# evalboard_v1_final.net
KiCad netlist of a schematic drawn in EAGLE
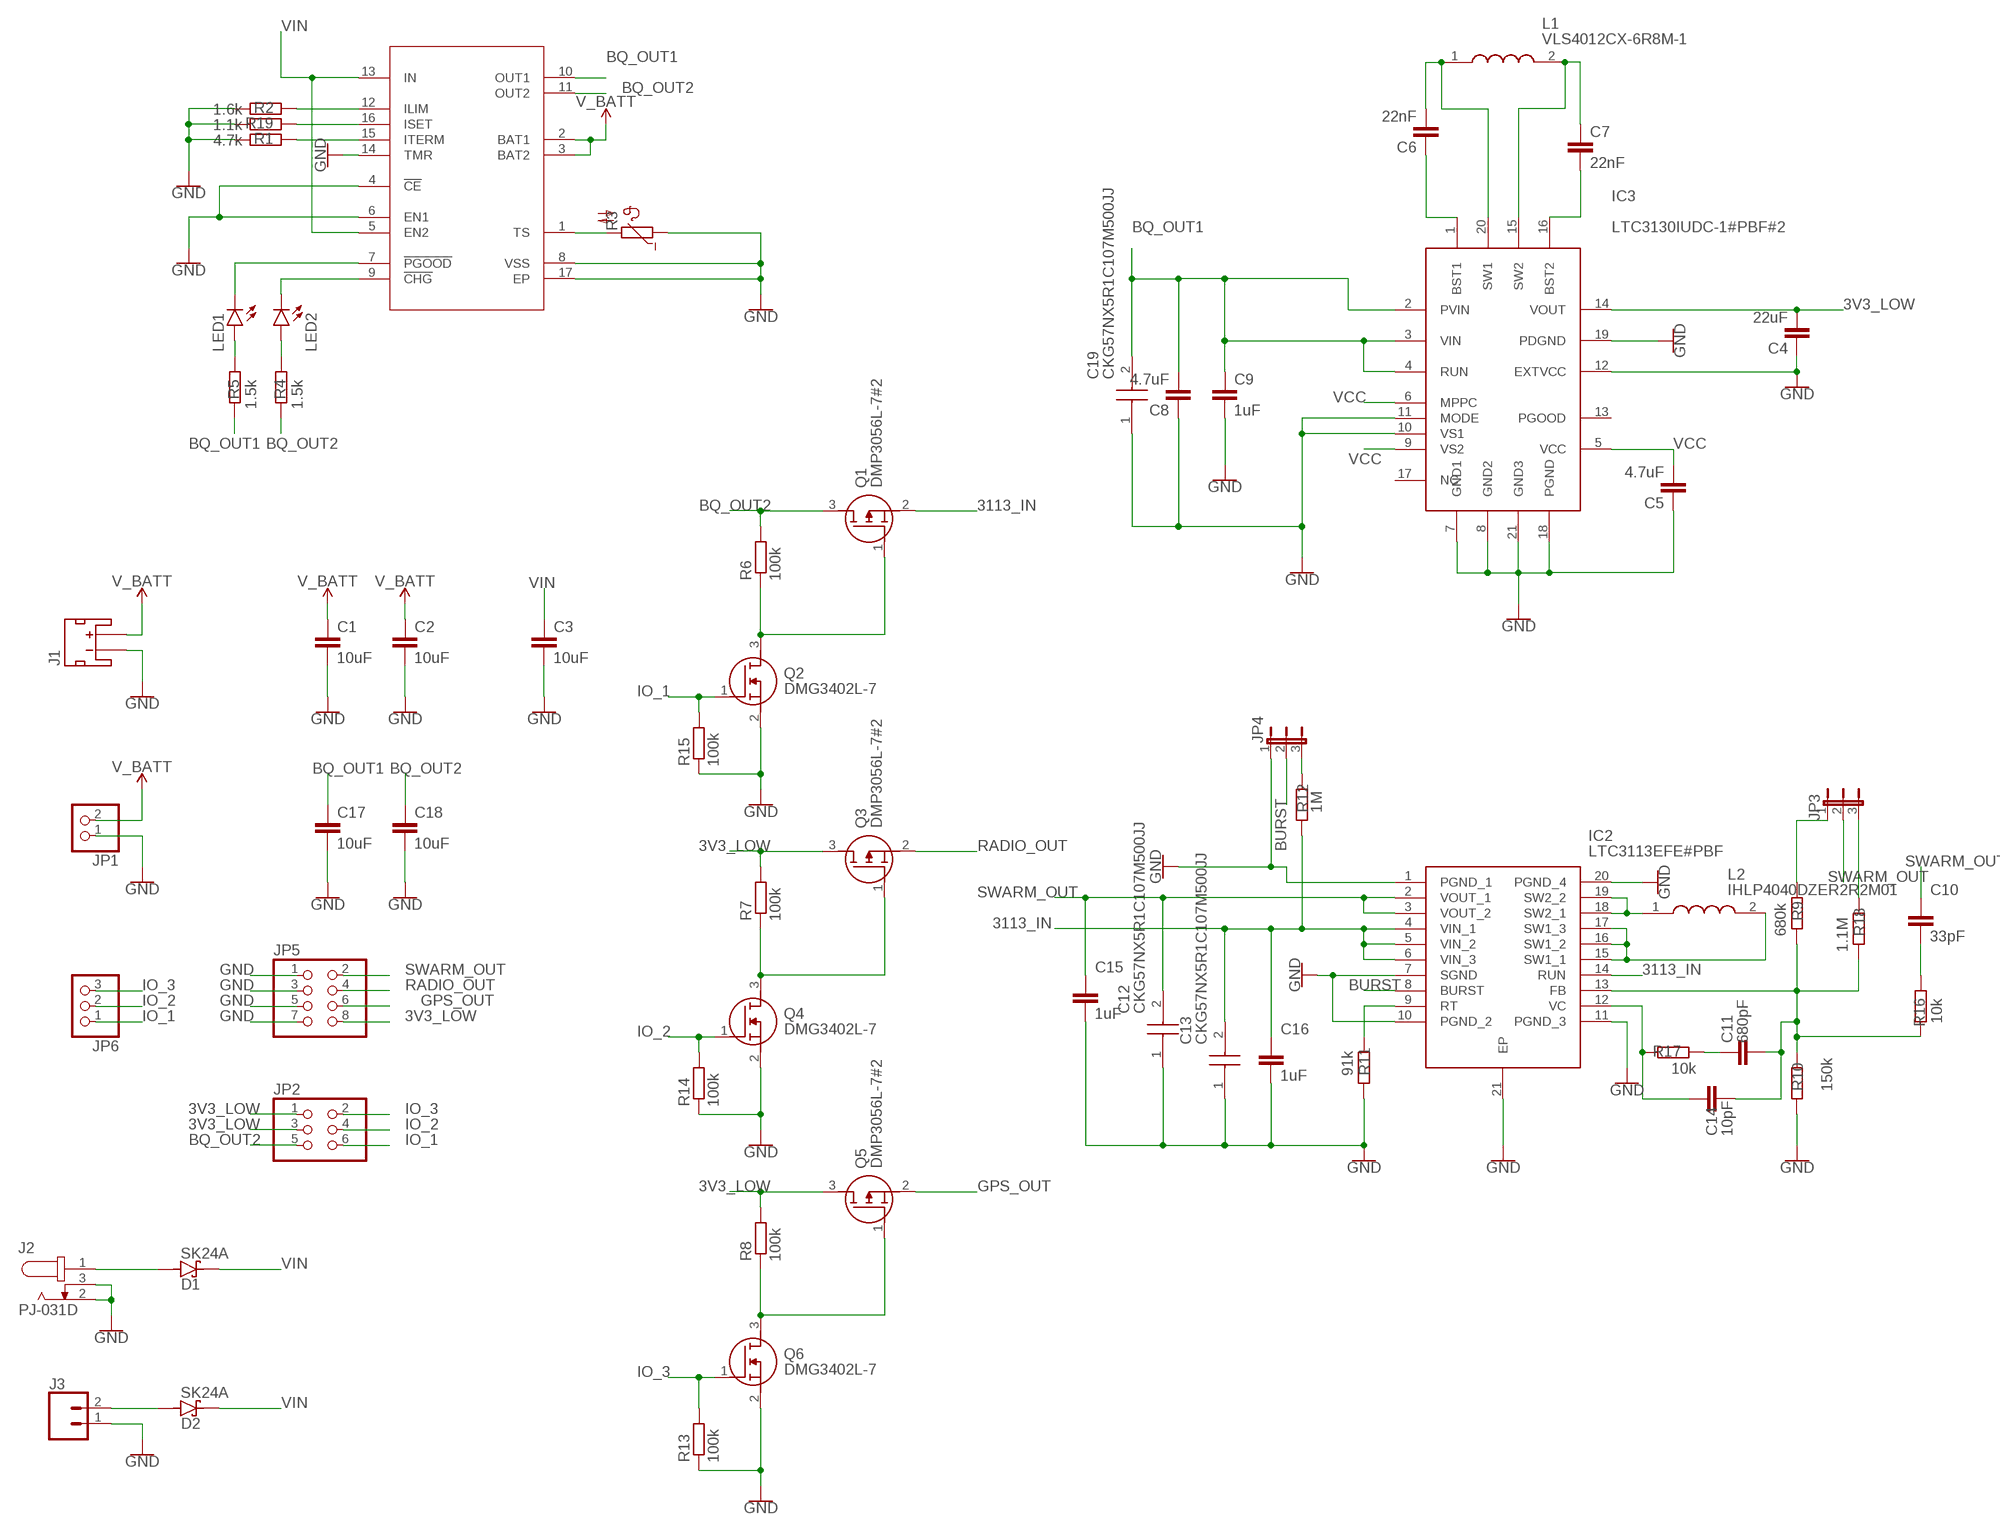
[diagram p0: schematic, sheet 1]

(export (version "E")
  (design (tool "Eeschema 10.0.6"))
  (components
    (comp (ref "C1")
      (value "10uF")
      (footprint "eagle-import:C1210")
      (libsource (lib "eagle-import") (part "C-EUC1210"))
    )
    (comp (ref "C2")
      (value "10uF")
      (footprint "eagle-import:C1210")
      (libsource (lib "eagle-import") (part "C-EUC1210"))
    )
    (comp (ref "C3")
      (value "10uF")
      (footprint "eagle-import:C1210")
      (libsource (lib "eagle-import") (part "C-EUC1210"))
    )
    (comp (ref "C4")
      (value "22uF")
      (footprint "eagle-import:C1210")
      (libsource (lib "eagle-import") (part "C-EUC1210"))
    )
    (comp (ref "C5")
      (value "4.7uF")
      (footprint "eagle-import:C1210")
      (libsource (lib "eagle-import") (part "C-EUC1210"))
    )
    (comp (ref "C6")
      (value "22nF")
      (footprint "eagle-import:C0603")
      (libsource (lib "eagle-import") (part "C-EUC0603"))
    )
    (comp (ref "C7")
      (value "22nF")
      (footprint "eagle-import:C0603")
      (libsource (lib "eagle-import") (part "C-EUC0603"))
    )
    (comp (ref "C8")
      (value "4.7uF")
      (footprint "eagle-import:C1210")
      (libsource (lib "eagle-import") (part "C-EUC1210"))
    )
    (comp (ref "C9")
      (value "1uF")
      (footprint "eagle-import:C0603")
      (libsource (lib "eagle-import") (part "C-EUC0603"))
    )
    (comp (ref "C10")
      (value "33pF")
      (footprint "eagle-import:C0603")
      (libsource (lib "eagle-import") (part "C-EUC0603"))
    )
    (comp (ref "C11")
      (value "680pF")
      (footprint "eagle-import:C0603")
      (libsource (lib "eagle-import") (part "C-EUC0603"))
    )
    (comp (ref "C12")
      (value "CKG57NX5R1C107M500JJ")
      (footprint "eagle-import:CAPC6050X550N")
      (fields (field (name "MOUSER_PART_NUMBER") "810-CKG57NX5R1C107MJ"))
      (libsource (lib "eagle-import") (part "CKG57NX5R1C107M500JJ"))
    )
    (comp (ref "C13")
      (value "CKG57NX5R1C107M500JJ")
      (footprint "eagle-import:CAPC6050X550N")
      (fields (field (name "MOUSER_PART_NUMBER") "810-CKG57NX5R1C107MJ"))
      (libsource (lib "eagle-import") (part "CKG57NX5R1C107M500JJ"))
    )
    (comp (ref "C14")
      (value "10pF")
      (footprint "eagle-import:C0603")
      (libsource (lib "eagle-import") (part "C-EUC0603"))
    )
    (comp (ref "C15")
      (value "1uF")
      (footprint "eagle-import:C0603")
      (libsource (lib "eagle-import") (part "C-EUC0603"))
    )
    (comp (ref "C16")
      (value "1uF")
      (footprint "eagle-import:C0603")
      (libsource (lib "eagle-import") (part "C-EUC0603"))
    )
    (comp (ref "C17")
      (value "10uF")
      (footprint "eagle-import:C1210")
      (libsource (lib "eagle-import") (part "C-EUC1210"))
    )
    (comp (ref "C18")
      (value "10uF")
      (footprint "eagle-import:C1210")
      (libsource (lib "eagle-import") (part "C-EUC1210"))
    )
    (comp (ref "C19")
      (value "CKG57NX5R1C107M500JJ")
      (footprint "eagle-import:CAPC6050X550N")
      (fields (field (name "MOUSER_PART_NUMBER") "810-CKG57NX5R1C107MJ"))
      (libsource (lib "eagle-import") (part "CKG57NX5R1C107M500JJ"))
    )
    (comp (ref "D1")
      (value "SK24A")
      (footprint "eagle-import:DIOM4325X250N")
      (fields (field (name "DIGI-KEY_PART_NUMBER") "1655-SK24ATR-ND") (field (name "MF") "SMC Diode"))
      (libsource (lib "eagle-import") (part "SK24A"))
    )
    (comp (ref "D2")
      (value "SK24A")
      (footprint "eagle-import:DIOM4325X250N")
      (fields (field (name "DIGI-KEY_PART_NUMBER") "1655-SK24ATR-ND") (field (name "MF") "SMC Diode"))
      (libsource (lib "eagle-import") (part "SK24A"))
    )
    (comp (ref "IC1")
      (value "BQ24074")
      (footprint "eagle-import:QFN50P300X300X100-17N")
      (libsource (lib "eagle-import") (part "BQ24074"))
    )
    (comp (ref "IC2")
      (value "LTC3113EFE#PBF")
      (footprint "eagle-import:SOP65P640X120-21N")
      (fields (field (name "MOUSER_PART_NUMBER") "584-LTC3113EFE#PBF"))
      (libsource (lib "eagle-import") (part "LTC3113EFE#PBF"))
    )
    (comp (ref "IC3")
      (value "LTC3130IUDC-1#PBF#2")
      (footprint "eagle-import:QFN50P300X400X80-21N")
      (fields (field (name "MANUFACTURER_PART_NUMBER") "LTC3130IUDC-1#PBF"))
      (libsource (lib "eagle-import") (part "LTC3130IUDC-1#PBF#2"))
    )
    (comp (ref "J1")
      (value "JST_2MM_MALE")
      (footprint "eagle-import:JST-2-SMD")
      (libsource (lib "eagle-import") (part "JST_2MM_MALE"))
    )
    (comp (ref "J2")
      (value "PJ-031D")
      (footprint "eagle-import:CUI_PJ-031D")
      (fields (field (name "MF") "CUI Devices"))
      (libsource (lib "eagle-import") (part "PJ-031D"))
    )
    (comp (ref "J3")
      (value "CONN_023.5MM")
      (footprint "eagle-import:SCREWTERMINAL-3.5MM-2")
      (libsource (lib "eagle-import") (part "CONN_023.5MM"))
    )
    (comp (ref "JP1")
      (value "PINHD-1X2")
      (footprint "eagle-import:1X02")
      (libsource (lib "eagle-import") (part "PINHD-1X2"))
    )
    (comp (ref "JP2")
      (value "PINHD-2X3")
      (footprint "eagle-import:2X03")
      (libsource (lib "eagle-import") (part "PINHD-2X3"))
    )
    (comp (ref "JP3")
      (value "JP2E")
      (footprint "eagle-import:JP2")
      (libsource (lib "eagle-import") (part "JP2E"))
    )
    (comp (ref "JP4")
      (value "JP2E")
      (footprint "eagle-import:JP2")
      (libsource (lib "eagle-import") (part "JP2E"))
    )
    (comp (ref "JP5")
      (value "PINHD-2X4")
      (footprint "eagle-import:2X04")
      (libsource (lib "eagle-import") (part "PINHD-2X4"))
    )
    (comp (ref "JP6")
      (value "PINHD-1X3")
      (footprint "eagle-import:1X03")
      (libsource (lib "eagle-import") (part "PINHD-1X3"))
    )
    (comp (ref "L1")
      (value "VLS4012CX-6R8M-1")
      (footprint "eagle-import:VLS4012")
      (libsource (lib "eagle-import") (part "VLS4012CX-6R8M-1"))
    )
    (comp (ref "L2")
      (value "IHLP4040DZER2R2M01")
      (footprint "eagle-import:INDPM108102X400N")
      (fields (field (name "MOUSER_PART_NUMBER") "70-IHLP4040DZER2R2M0"))
      (libsource (lib "eagle-import") (part "IHLP4040DZER2R2M01"))
    )
    (comp (ref "LED1")
      (value "LEDCHIP-LED0603")
      (footprint "eagle-import:CHIP-LED0603")
      (libsource (lib "eagle-import") (part "LEDCHIP-LED0603"))
    )
    (comp (ref "LED2")
      (value "LEDCHIP-LED0603")
      (footprint "eagle-import:CHIP-LED0603")
      (libsource (lib "eagle-import") (part "LEDCHIP-LED0603"))
    )
    (comp (ref "Q1")
      (value "DMP3056L-7#2")
      (footprint "eagle-import:SOT96P240X100-3N")
      (fields
        (field (name "ARROW_PART_NUMBER") "DMP3056L-7")
        (field (name "MOUSER_PART_NUMBER") "621-DMP3056L-7")
      )
      (libsource (lib "eagle-import") (part "DMP3056L-7#2"))
    )
    (comp (ref "Q2")
      (value "DMG3402L-7")
      (footprint "eagle-import:SOT96P240X110-3N")
      (fields (field (name "MOUSER_PART_NUMBER") "621-DMG3402L-7"))
      (libsource (lib "eagle-import") (part "DMG3402L-7"))
    )
    (comp (ref "Q3")
      (value "DMP3056L-7#2")
      (footprint "eagle-import:SOT96P240X100-3N")
      (fields
        (field (name "ARROW_PART_NUMBER") "DMP3056L-7")
        (field (name "MOUSER_PART_NUMBER") "621-DMP3056L-7")
      )
      (libsource (lib "eagle-import") (part "DMP3056L-7#2"))
    )
    (comp (ref "Q4")
      (value "DMG3402L-7")
      (footprint "eagle-import:SOT96P240X110-3N")
      (fields (field (name "MOUSER_PART_NUMBER") "621-DMG3402L-7"))
      (libsource (lib "eagle-import") (part "DMG3402L-7"))
    )
    (comp (ref "Q5")
      (value "DMP3056L-7#2")
      (footprint "eagle-import:SOT96P240X100-3N")
      (fields
        (field (name "ARROW_PART_NUMBER") "DMP3056L-7")
        (field (name "MOUSER_PART_NUMBER") "621-DMP3056L-7")
      )
      (libsource (lib "eagle-import") (part "DMP3056L-7#2"))
    )
    (comp (ref "Q6")
      (value "DMG3402L-7")
      (footprint "eagle-import:SOT96P240X110-3N")
      (fields (field (name "MOUSER_PART_NUMBER") "621-DMG3402L-7"))
      (libsource (lib "eagle-import") (part "DMG3402L-7"))
    )
    (comp (ref "R1")
      (value "4.7k")
      (footprint "eagle-import:R0603")
      (libsource (lib "eagle-import") (part "R-EU_R0603"))
    )
    (comp (ref "R2")
      (value "1.6k")
      (footprint "eagle-import:R0603")
      (libsource (lib "eagle-import") (part "R-EU_R0603"))
    )
    (comp (ref "R3")
      (value "10k")
      (footprint "eagle-import:P640")
      (libsource (lib "eagle-import") (part "NTC640"))
    )
    (comp (ref "R4")
      (value "1.5k")
      (footprint "eagle-import:R0603")
      (libsource (lib "eagle-import") (part "R-EU_R0603"))
    )
    (comp (ref "R5")
      (value "1.5k")
      (footprint "eagle-import:R0603")
      (libsource (lib "eagle-import") (part "R-EU_R0603"))
    )
    (comp (ref "R6")
      (value "100k")
      (footprint "eagle-import:R0603")
      (libsource (lib "eagle-import") (part "R-EU_R0603"))
    )
    (comp (ref "R7")
      (value "100k")
      (footprint "eagle-import:R0603")
      (libsource (lib "eagle-import") (part "R-EU_R0603"))
    )
    (comp (ref "R8")
      (value "100k")
      (footprint "eagle-import:R0603")
      (libsource (lib "eagle-import") (part "R-EU_R0603"))
    )
    (comp (ref "R9")
      (value "680k")
      (footprint "eagle-import:R0603")
      (libsource (lib "eagle-import") (part "R-EU_R0603"))
    )
    (comp (ref "R10")
      (value "150k")
      (footprint "eagle-import:R0603")
      (libsource (lib "eagle-import") (part "R-EU_R0603"))
    )
    (comp (ref "R11")
      (value "91k")
      (footprint "eagle-import:R0603")
      (libsource (lib "eagle-import") (part "R-EU_R0603"))
    )
    (comp (ref "R12")
      (value "1M")
      (footprint "eagle-import:R0603")
      (libsource (lib "eagle-import") (part "R-EU_R0603"))
    )
    (comp (ref "R13")
      (value "100k")
      (footprint "eagle-import:R0603")
      (libsource (lib "eagle-import") (part "R-EU_R0603"))
    )
    (comp (ref "R14")
      (value "100k")
      (footprint "eagle-import:R0603")
      (libsource (lib "eagle-import") (part "R-EU_R0603"))
    )
    (comp (ref "R15")
      (value "100k")
      (footprint "eagle-import:R0603")
      (libsource (lib "eagle-import") (part "R-EU_R0603"))
    )
    (comp (ref "R16")
      (value "10k")
      (footprint "eagle-import:R0603")
      (libsource (lib "eagle-import") (part "R-EU_R0603"))
    )
    (comp (ref "R17")
      (value "10k")
      (footprint "eagle-import:R0603")
      (libsource (lib "eagle-import") (part "R-EU_R0603"))
    )
    (comp (ref "R18")
      (value "1.1M")
      (footprint "eagle-import:R0603")
      (libsource (lib "eagle-import") (part "R-EU_R0603"))
    )
    (comp (ref "R19")
      (value "1.1k")
      (footprint "eagle-import:R0603")
      (libsource (lib "eagle-import") (part "R-EU_R0603"))
    )
  )
  (nets
    (net (code "1") (name "/3V3_LOW") (class "Default")
      (node (ref "C4") (pin "2") (pinfunction "2_2") (pintype "passive"))
      (node (ref "IC3") (pin "14") (pinfunction "VOUT_14") (pintype "output"))
      (node (ref "JP2") (pin "1") (pinfunction "1_1") (pintype "passive"))
      (node (ref "JP2") (pin "3") (pinfunction "3_3") (pintype "passive"))
      (node (ref "JP5") (pin "8") (pinfunction "8_8") (pintype "passive"))
      (node (ref "Q3") (pin "3") (pinfunction "D_3") (pintype "bidirectional"))
      (node (ref "Q5") (pin "3") (pinfunction "D_3") (pintype "bidirectional"))
      (node (ref "R7") (pin "2") (pinfunction "2_2") (pintype "passive"))
      (node (ref "R8") (pin "2") (pinfunction "2_2") (pintype "passive"))
    )
    (net (code "2") (name "/3113_IN") (class "Default")
      (node (ref "C13") (pin "2") (pinfunction "2_2") (pintype "bidirectional"))
      (node (ref "C16") (pin "1") (pinfunction "1_1") (pintype "passive"))
      (node (ref "IC2") (pin "14") (pinfunction "RUN_14") (pintype "bidirectional"))
      (node (ref "IC2") (pin "4") (pinfunction "VIN_1_4") (pintype "bidirectional"))
      (node (ref "IC2") (pin "5") (pinfunction "VIN_2_5") (pintype "bidirectional"))
      (node (ref "IC2") (pin "6") (pinfunction "VIN_3_6") (pintype "bidirectional"))
      (node (ref "Q1") (pin "2") (pinfunction "S_2") (pintype "bidirectional"))
      (node (ref "R12") (pin "1") (pinfunction "1_1") (pintype "passive"))
    )
    (net (code "3") (name "/BQ_OUT1") (class "Default")
      (node (ref "C17") (pin "1") (pinfunction "1_1") (pintype "passive"))
      (node (ref "C19") (pin "2") (pinfunction "2_2") (pintype "bidirectional"))
      (node (ref "C8") (pin "2") (pinfunction "2_2") (pintype "passive"))
      (node (ref "C9") (pin "1") (pinfunction "1_1") (pintype "passive"))
      (node (ref "IC1") (pin "10") (pinfunction "OUT1_10") (pintype "bidirectional"))
      (node (ref "IC3") (pin "2") (pinfunction "PVIN_2") (pintype "input"))
      (node (ref "IC3") (pin "3") (pinfunction "VIN_3") (pintype "input"))
      (node (ref "IC3") (pin "4") (pinfunction "RUN_4") (pintype "bidirectional"))
      (node (ref "R5") (pin "2") (pinfunction "2_2") (pintype "passive"))
    )
    (net (code "4") (name "/BQ_OUT2") (class "Default")
      (node (ref "C18") (pin "1") (pinfunction "1_1") (pintype "passive"))
      (node (ref "IC1") (pin "11") (pinfunction "OUT2_11") (pintype "bidirectional"))
      (node (ref "JP2") (pin "5") (pinfunction "5_5") (pintype "passive"))
      (node (ref "Q1") (pin "3") (pinfunction "D_3") (pintype "bidirectional"))
      (node (ref "R4") (pin "2") (pinfunction "2_2") (pintype "passive"))
      (node (ref "R6") (pin "2") (pinfunction "2_2") (pintype "passive"))
    )
    (net (code "5") (name "/BURST") (class "Default")
      (node (ref "IC2") (pin "8") (pinfunction "BURST_8") (pintype "bidirectional"))
      (node (ref "JP4") (pin "2") (pinfunction "2_2") (pintype "passive"))
    )
    (net (code "6") (name "/GPS_OUT") (class "Default")
      (node (ref "JP5") (pin "6") (pinfunction "6_6") (pintype "passive"))
      (node (ref "Q5") (pin "2") (pinfunction "S_2") (pintype "bidirectional"))
    )
    (net (code "7") (name "/IO_1") (class "Default")
      (node (ref "JP2") (pin "6") (pinfunction "6_6") (pintype "passive"))
      (node (ref "JP6") (pin "1") (pinfunction "1_1") (pintype "passive"))
      (node (ref "Q2") (pin "1") (pinfunction "G_1") (pintype "bidirectional"))
      (node (ref "R15") (pin "2") (pinfunction "2_2") (pintype "passive"))
    )
    (net (code "8") (name "/IO_2") (class "Default")
      (node (ref "JP2") (pin "4") (pinfunction "4_4") (pintype "passive"))
      (node (ref "JP6") (pin "2") (pinfunction "2_2") (pintype "passive"))
      (node (ref "Q4") (pin "1") (pinfunction "G_1") (pintype "bidirectional"))
      (node (ref "R14") (pin "2") (pinfunction "2_2") (pintype "passive"))
    )
    (net (code "9") (name "/IO_3") (class "Default")
      (node (ref "JP2") (pin "2") (pinfunction "2_2") (pintype "passive"))
      (node (ref "JP6") (pin "3") (pinfunction "3_3") (pintype "passive"))
      (node (ref "Q6") (pin "1") (pinfunction "G_1") (pintype "bidirectional"))
      (node (ref "R13") (pin "2") (pinfunction "2_2") (pintype "passive"))
    )
    (net (code "10") (name "/RADIO_OUT") (class "Default")
      (node (ref "JP5") (pin "4") (pinfunction "4_4") (pintype "passive"))
      (node (ref "Q3") (pin "2") (pinfunction "S_2") (pintype "bidirectional"))
    )
    (net (code "11") (name "/SWARM_OUT") (class "Default")
      (node (ref "C10") (pin "1") (pinfunction "1_1") (pintype "passive"))
      (node (ref "C12") (pin "2") (pinfunction "2_2") (pintype "bidirectional"))
      (node (ref "C15") (pin "1") (pinfunction "1_1") (pintype "passive"))
      (node (ref "IC2") (pin "2") (pinfunction "VOUT_1_2") (pintype "bidirectional"))
      (node (ref "IC2") (pin "3") (pinfunction "VOUT_2_3") (pintype "bidirectional"))
      (node (ref "JP3") (pin "2") (pinfunction "2_2") (pintype "passive"))
      (node (ref "JP5") (pin "2") (pinfunction "2_2") (pintype "passive"))
    )
    (net (code "12") (name "/VCC") (class "Default")
      (node (ref "C5") (pin "2") (pinfunction "2_2") (pintype "passive"))
      (node (ref "IC3") (pin "5") (pinfunction "VCC_5") (pintype "bidirectional"))
      (node (ref "IC3") (pin "6") (pinfunction "MPPC_6") (pintype "bidirectional"))
      (node (ref "IC3") (pin "9") (pinfunction "VS2_9") (pintype "bidirectional"))
    )
    (net (code "13") (name "/VIN") (class "Default")
      (node (ref "C3") (pin "1") (pinfunction "1_1") (pintype "passive"))
      (node (ref "D1") (pin "C") (pinfunction "K_C") (pintype "passive"))
      (node (ref "D2") (pin "C") (pinfunction "K_C") (pintype "passive"))
      (node (ref "IC1") (pin "13") (pinfunction "IN_13") (pintype "bidirectional"))
      (node (ref "IC1") (pin "5") (pinfunction "EN2_5") (pintype "bidirectional"))
    )
    (net (code "14") (name "GND") (class "Default")
      (node (ref "C1") (pin "2") (pinfunction "2_2") (pintype "passive"))
      (node (ref "C12") (pin "1") (pinfunction "1_1") (pintype "bidirectional"))
      (node (ref "C13") (pin "1") (pinfunction "1_1") (pintype "bidirectional"))
      (node (ref "C15") (pin "2") (pinfunction "2_2") (pintype "passive"))
      (node (ref "C16") (pin "2") (pinfunction "2_2") (pintype "passive"))
      (node (ref "C17") (pin "2") (pinfunction "2_2") (pintype "passive"))
      (node (ref "C18") (pin "2") (pinfunction "2_2") (pintype "passive"))
      (node (ref "C19") (pin "1") (pinfunction "1_1") (pintype "bidirectional"))
      (node (ref "C2") (pin "2") (pinfunction "2_2") (pintype "passive"))
      (node (ref "C3") (pin "2") (pinfunction "2_2") (pintype "passive"))
      (node (ref "C4") (pin "1") (pinfunction "1_1") (pintype "passive"))
      (node (ref "C5") (pin "1") (pinfunction "1_1") (pintype "passive"))
      (node (ref "C8") (pin "1") (pinfunction "1_1") (pintype "passive"))
      (node (ref "C9") (pin "2") (pinfunction "2_2") (pintype "passive"))
      (node (ref "IC1") (pin "14") (pinfunction "TMR_14") (pintype "bidirectional"))
      (node (ref "IC1") (pin "17") (pinfunction "EP_17") (pintype "bidirectional"))
      (node (ref "IC1") (pin "4") (pinfunction "~{CE}_4") (pintype "bidirectional"))
      (node (ref "IC1") (pin "6") (pinfunction "EN1_6") (pintype "bidirectional"))
      (node (ref "IC1") (pin "8") (pinfunction "VSS_8") (pintype "bidirectional"))
      (node (ref "IC2") (pin "1") (pinfunction "PGND_1_1") (pintype "bidirectional"))
      (node (ref "IC2") (pin "10") (pinfunction "PGND_2_10") (pintype "bidirectional"))
      (node (ref "IC2") (pin "11") (pinfunction "PGND_3_11") (pintype "bidirectional"))
      (node (ref "IC2") (pin "20") (pinfunction "PGND_4_20") (pintype "bidirectional"))
      (node (ref "IC2") (pin "21") (pinfunction "EP_21") (pintype "bidirectional"))
      (node (ref "IC2") (pin "7") (pinfunction "SGND_7") (pintype "bidirectional"))
      (node (ref "IC3") (pin "10") (pinfunction "VS1_10") (pintype "bidirectional"))
      (node (ref "IC3") (pin "11") (pinfunction "MODE_11") (pintype "bidirectional"))
      (node (ref "IC3") (pin "12") (pinfunction "EXTVCC_12") (pintype "bidirectional"))
      (node (ref "IC3") (pin "18") (pinfunction "PGND_18") (pintype "bidirectional"))
      (node (ref "IC3") (pin "19") (pinfunction "PDGND_19") (pintype "bidirectional"))
      (node (ref "IC3") (pin "21") (pinfunction "GND3_21") (pintype "bidirectional"))
      (node (ref "IC3") (pin "7") (pinfunction "GND1_7") (pintype "bidirectional"))
      (node (ref "IC3") (pin "8") (pinfunction "GND2_8") (pintype "bidirectional"))
      (node (ref "J1") (pin "1") (pinfunction "-_1") (pintype "bidirectional"))
      (node (ref "J2") (pin "2") (pinfunction "2_2") (pintype "passive"))
      (node (ref "J2") (pin "3") (pinfunction "3_3") (pintype "passive"))
      (node (ref "J3") (pin "1") (pinfunction "1_1") (pintype "passive"))
      (node (ref "JP1") (pin "1") (pinfunction "1_1") (pintype "passive"))
      (node (ref "JP4") (pin "1") (pinfunction "1_1") (pintype "passive"))
      (node (ref "JP5") (pin "1") (pinfunction "1_1") (pintype "passive"))
      (node (ref "JP5") (pin "3") (pinfunction "3_3") (pintype "passive"))
      (node (ref "JP5") (pin "5") (pinfunction "5_5") (pintype "passive"))
      (node (ref "JP5") (pin "7") (pinfunction "7_7") (pintype "passive"))
      (node (ref "Q2") (pin "2") (pinfunction "S_2") (pintype "bidirectional"))
      (node (ref "Q4") (pin "2") (pinfunction "S_2") (pintype "bidirectional"))
      (node (ref "Q6") (pin "2") (pinfunction "S_2") (pintype "bidirectional"))
      (node (ref "R1") (pin "2") (pinfunction "2_2") (pintype "passive"))
      (node (ref "R10") (pin "1") (pinfunction "1_1") (pintype "passive"))
      (node (ref "R11") (pin "1") (pinfunction "1_1") (pintype "passive"))
      (node (ref "R13") (pin "1") (pinfunction "1_1") (pintype "passive"))
      (node (ref "R14") (pin "1") (pinfunction "1_1") (pintype "passive"))
      (node (ref "R15") (pin "1") (pinfunction "1_1") (pintype "passive"))
      (node (ref "R19") (pin "2") (pinfunction "2_2") (pintype "passive"))
      (node (ref "R2") (pin "2") (pinfunction "2_2") (pintype "passive"))
      (node (ref "R3") (pin "1") (pinfunction "1_1") (pintype "passive"))
    )
    (net (code "15") (name "Net-(C10-Pad2)") (class "Default")
      (node (ref "C10") (pin "2") (pinfunction "2_2") (pintype "passive"))
      (node (ref "R16") (pin "1") (pinfunction "1_1") (pintype "passive"))
    )
    (net (code "16") (name "Net-(C11-Pad1)") (class "Default")
      (node (ref "C11") (pin "1") (pinfunction "1_1") (pintype "passive"))
      (node (ref "R17") (pin "1") (pinfunction "1_1") (pintype "passive"))
    )
    (net (code "17") (name "Net-(D1-PadA)") (class "Default")
      (node (ref "D1") (pin "A") (pinfunction "A_A") (pintype "passive"))
      (node (ref "J2") (pin "1") (pinfunction "1_1") (pintype "passive"))
    )
    (net (code "18") (name "Net-(D2-PadA)") (class "Default")
      (node (ref "D2") (pin "A") (pinfunction "A_A") (pintype "passive"))
      (node (ref "J3") (pin "2") (pinfunction "2_2") (pintype "passive"))
    )
    (net (code "19") (name "Net-(IC1-ILIM)") (class "Default")
      (node (ref "IC1") (pin "12") (pinfunction "ILIM_12") (pintype "bidirectional"))
      (node (ref "R2") (pin "1") (pinfunction "1_1") (pintype "passive"))
    )
    (net (code "20") (name "Net-(IC1-ISET)") (class "Default")
      (node (ref "IC1") (pin "16") (pinfunction "ISET_16") (pintype "bidirectional"))
      (node (ref "R19") (pin "1") (pinfunction "1_1") (pintype "passive"))
    )
    (net (code "21") (name "Net-(IC1-ITERM)") (class "Default")
      (node (ref "IC1") (pin "15") (pinfunction "ITERM_15") (pintype "bidirectional"))
      (node (ref "R1") (pin "1") (pinfunction "1_1") (pintype "passive"))
    )
    (net (code "22") (name "Net-(IC1-TS)") (class "Default")
      (node (ref "IC1") (pin "1") (pinfunction "TS_1") (pintype "bidirectional"))
      (node (ref "R3") (pin "2") (pinfunction "2_2") (pintype "passive"))
    )
    (net (code "23") (name "Net-(IC1-~{CHG})") (class "Default")
      (node (ref "IC1") (pin "9") (pinfunction "~{CHG}_9") (pintype "bidirectional"))
      (node (ref "LED2") (pin "C") (pinfunction "C_C") (pintype "passive"))
    )
    (net (code "24") (name "Net-(IC1-~{PGOOD})") (class "Default")
      (node (ref "IC1") (pin "7") (pinfunction "~{PGOOD}_7") (pintype "bidirectional"))
      (node (ref "LED1") (pin "C") (pinfunction "C_C") (pintype "passive"))
    )
    (net (code "25") (name "Net-(IC2-FB)") (class "Default")
      (node (ref "C11") (pin "2") (pinfunction "2_2") (pintype "passive"))
      (node (ref "C14") (pin "2") (pinfunction "2_2") (pintype "passive"))
      (node (ref "IC2") (pin "13") (pinfunction "FB_13") (pintype "bidirectional"))
      (node (ref "R10") (pin "2") (pinfunction "2_2") (pintype "passive"))
      (node (ref "R16") (pin "2") (pinfunction "2_2") (pintype "passive"))
      (node (ref "R18") (pin "1") (pinfunction "1_1") (pintype "passive"))
      (node (ref "R9") (pin "1") (pinfunction "1_1") (pintype "passive"))
    )
    (net (code "26") (name "Net-(IC2-RT)") (class "Default")
      (node (ref "IC2") (pin "9") (pinfunction "RT_9") (pintype "bidirectional"))
      (node (ref "R11") (pin "2") (pinfunction "2_2") (pintype "passive"))
    )
    (net (code "27") (name "Net-(IC2-SW1_1)") (class "Default")
      (node (ref "IC2") (pin "15") (pinfunction "SW1_1_15") (pintype "bidirectional"))
      (node (ref "IC2") (pin "16") (pinfunction "SW1_2_16") (pintype "bidirectional"))
      (node (ref "IC2") (pin "17") (pinfunction "SW1_3_17") (pintype "bidirectional"))
      (node (ref "L2") (pin "2") (pinfunction "2_2") (pintype "bidirectional"))
    )
    (net (code "28") (name "Net-(IC2-SW2_1)") (class "Default")
      (node (ref "IC2") (pin "18") (pinfunction "SW2_1_18") (pintype "bidirectional"))
      (node (ref "IC2") (pin "19") (pinfunction "SW2_2_19") (pintype "bidirectional"))
      (node (ref "L2") (pin "1") (pinfunction "1_1") (pintype "bidirectional"))
    )
    (net (code "29") (name "Net-(IC2-VC)") (class "Default")
      (node (ref "C14") (pin "1") (pinfunction "1_1") (pintype "passive"))
      (node (ref "IC2") (pin "12") (pinfunction "VC_12") (pintype "bidirectional"))
      (node (ref "R17") (pin "2") (pinfunction "2_2") (pintype "passive"))
    )
    (net (code "30") (name "Net-(IC3-BST1)") (class "Default")
      (node (ref "C6") (pin "1") (pinfunction "1_1") (pintype "passive"))
      (node (ref "IC3") (pin "1") (pinfunction "BST1_1") (pintype "bidirectional"))
    )
    (net (code "31") (name "Net-(IC3-BST2)") (class "Default")
      (node (ref "C7") (pin "2") (pinfunction "2_2") (pintype "passive"))
      (node (ref "IC3") (pin "16") (pinfunction "BST2_16") (pintype "bidirectional"))
    )
    (net (code "32") (name "Net-(IC3-SW1)") (class "Default")
      (node (ref "C6") (pin "2") (pinfunction "2_2") (pintype "passive"))
      (node (ref "IC3") (pin "20") (pinfunction "SW1_20") (pintype "bidirectional"))
      (node (ref "L1") (pin "1") (pinfunction "1_1") (pintype "bidirectional"))
    )
    (net (code "33") (name "Net-(IC3-SW2)") (class "Default")
      (node (ref "C7") (pin "1") (pinfunction "1_1") (pintype "passive"))
      (node (ref "IC3") (pin "15") (pinfunction "SW2_15") (pintype "bidirectional"))
      (node (ref "L1") (pin "2") (pinfunction "2_2") (pintype "bidirectional"))
    )
    (net (code "34") (name "Net-(JP3-Pad1)") (class "Default")
      (node (ref "JP3") (pin "1") (pinfunction "1_1") (pintype "passive"))
      (node (ref "R9") (pin "2") (pinfunction "2_2") (pintype "passive"))
    )
    (net (code "35") (name "Net-(JP3-Pad3)") (class "Default")
      (node (ref "JP3") (pin "3") (pinfunction "3_3") (pintype "passive"))
      (node (ref "R18") (pin "2") (pinfunction "2_2") (pintype "passive"))
    )
    (net (code "36") (name "Net-(JP4-Pad3)") (class "Default")
      (node (ref "JP4") (pin "3") (pinfunction "3_3") (pintype "passive"))
      (node (ref "R12") (pin "2") (pinfunction "2_2") (pintype "passive"))
    )
    (net (code "37") (name "Net-(LED1-PadA)") (class "Default")
      (node (ref "LED1") (pin "A") (pinfunction "A_A") (pintype "passive"))
      (node (ref "R5") (pin "1") (pinfunction "1_1") (pintype "passive"))
    )
    (net (code "38") (name "Net-(LED2-PadA)") (class "Default")
      (node (ref "LED2") (pin "A") (pinfunction "A_A") (pintype "passive"))
      (node (ref "R4") (pin "1") (pinfunction "1_1") (pintype "passive"))
    )
    (net (code "39") (name "Net-(Q1-G)") (class "Default")
      (node (ref "Q1") (pin "1") (pinfunction "G_1") (pintype "bidirectional"))
      (node (ref "Q2") (pin "3") (pinfunction "D_3") (pintype "bidirectional"))
      (node (ref "R6") (pin "1") (pinfunction "1_1") (pintype "passive"))
    )
    (net (code "40") (name "Net-(Q3-G)") (class "Default")
      (node (ref "Q3") (pin "1") (pinfunction "G_1") (pintype "bidirectional"))
      (node (ref "Q4") (pin "3") (pinfunction "D_3") (pintype "bidirectional"))
      (node (ref "R7") (pin "1") (pinfunction "1_1") (pintype "passive"))
    )
    (net (code "41") (name "Net-(Q5-G)") (class "Default")
      (node (ref "Q5") (pin "1") (pinfunction "G_1") (pintype "bidirectional"))
      (node (ref "Q6") (pin "3") (pinfunction "D_3") (pintype "bidirectional"))
      (node (ref "R8") (pin "1") (pinfunction "1_1") (pintype "passive"))
    )
    (net (code "42") (name "V_BATT") (class "Default")
      (node (ref "C1") (pin "1") (pinfunction "1_1") (pintype "passive"))
      (node (ref "C2") (pin "1") (pinfunction "1_1") (pintype "passive"))
      (node (ref "IC1") (pin "2") (pinfunction "BAT1_2") (pintype "bidirectional"))
      (node (ref "IC1") (pin "3") (pinfunction "BAT2_3") (pintype "bidirectional"))
      (node (ref "J1") (pin "2") (pinfunction "+_2") (pintype "bidirectional"))
      (node (ref "JP1") (pin "2") (pinfunction "2_2") (pintype "passive"))
    )
    (net (code "43") (name "unconnected-(IC3-NC-Pad17)") (class "Default")
      (node (ref "IC3") (pin "17") (pinfunction "NC_17") (pintype "bidirectional"))
    )
    (net (code "44") (name "unconnected-(IC3-PGOOD-Pad13)") (class "Default")
      (node (ref "IC3") (pin "13") (pinfunction "PGOOD_13") (pintype "bidirectional"))
    )
    (net (code "45") (name "unconnected-(J1-PAD1-PadNC1)") (class "Default")
      (node (ref "J1") (pin "NC1") (pinfunction "PAD1_NC1") (pintype "bidirectional"))
    )
    (net (code "46") (name "unconnected-(J1-PAD2-PadNC2)") (class "Default")
      (node (ref "J1") (pin "NC2") (pinfunction "PAD2_NC2") (pintype "bidirectional"))
    )
  )
)
